# ball_catch_unit_back.net
KiCad netlist of a schematic drawn in EAGLE
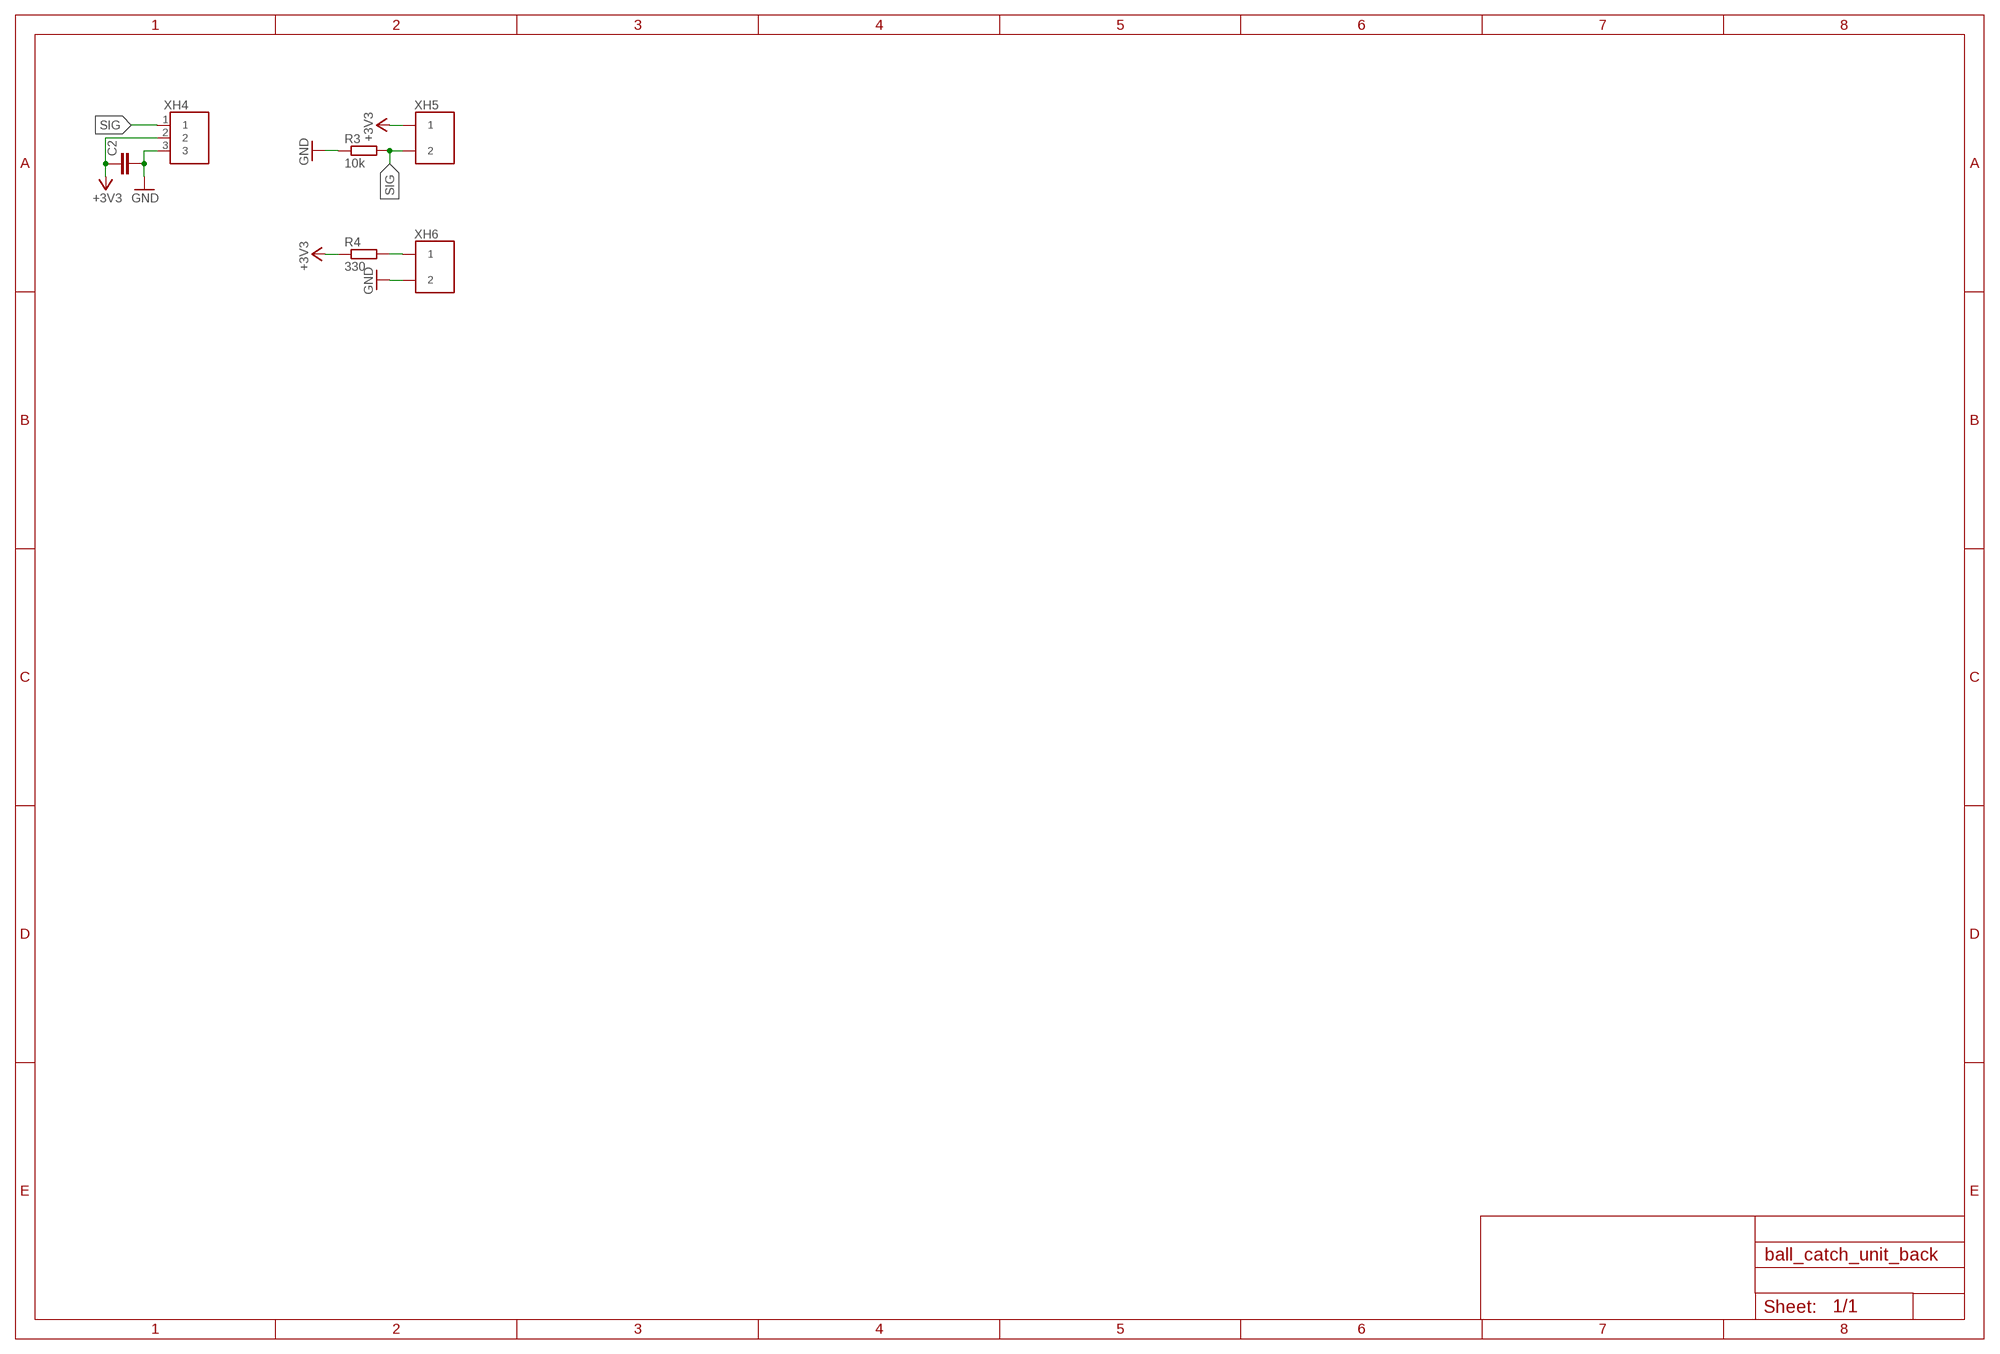
[diagram p0: schematic, sheet 1]

(export (version "E")
  (design (tool "Eeschema 10.0.6"))
  (components
    (comp (ref "C2")
      (value "C-EUC0603")
      (footprint "eagle-import:C0603")
      (libsource (lib "eagle-import") (part "C-EUC0603"))
    )
    (comp (ref "R3")
      (value "10k")
      (footprint "eagle-import:0204_7")
      (libsource (lib "eagle-import") (part "R-EU_0204/7"))
    )
    (comp (ref "R4")
      (value "330")
      (footprint "eagle-import:0204_7")
      (libsource (lib "eagle-import") (part "R-EU_0204/7"))
    )
    (comp (ref "XH4")
      (value "S3B")
      (footprint "eagle-import:S3B")
      (libsource (lib "eagle-import") (part "S3B"))
    )
    (comp (ref "XH5") (value "2B") (footprint "eagle-import:2B") (libsource (lib "eagle-import") (part "2B")))
    (comp (ref "XH6")
      (value "S2B")
      (footprint "eagle-import:S2B")
      (libsource (lib "eagle-import") (part "S2B"))
    )
  )
  (nets
    (net (code "1") (name "+3V3") (class "Default")
      (node (ref "C2") (pin "1") (pinfunction "1_1") (pintype "passive"))
      (node (ref "R4") (pin "1") (pinfunction "1_1") (pintype "passive"))
      (node (ref "XH4") (pin "2") (pinfunction "2_2") (pintype "bidirectional"))
      (node (ref "XH5") (pin "1") (pinfunction "1_1") (pintype "bidirectional"))
    )
    (net (code "2") (name "GND") (class "Default")
      (node (ref "C2") (pin "2") (pinfunction "2_2") (pintype "passive"))
      (node (ref "R3") (pin "1") (pinfunction "1_1") (pintype "passive"))
      (node (ref "XH4") (pin "3") (pinfunction "3_3") (pintype "bidirectional"))
      (node (ref "XH6") (pin "2") (pinfunction "2_2") (pintype "bidirectional"))
    )
    (net (code "3") (name "Net-(R4-Pad2)") (class "Default")
      (node (ref "R4") (pin "2") (pinfunction "2_2") (pintype "passive"))
      (node (ref "XH6") (pin "1") (pinfunction "1_1") (pintype "bidirectional"))
    )
    (net (code "4") (name "SIG") (class "Default")
      (node (ref "R3") (pin "2") (pinfunction "2_2") (pintype "passive"))
      (node (ref "XH4") (pin "1") (pinfunction "1_1") (pintype "bidirectional"))
      (node (ref "XH5") (pin "2") (pinfunction "2_2") (pintype "bidirectional"))
    )
  )
)
